# Sche_Main.net
KiCad netlist of a schematic drawn in Altium Designer
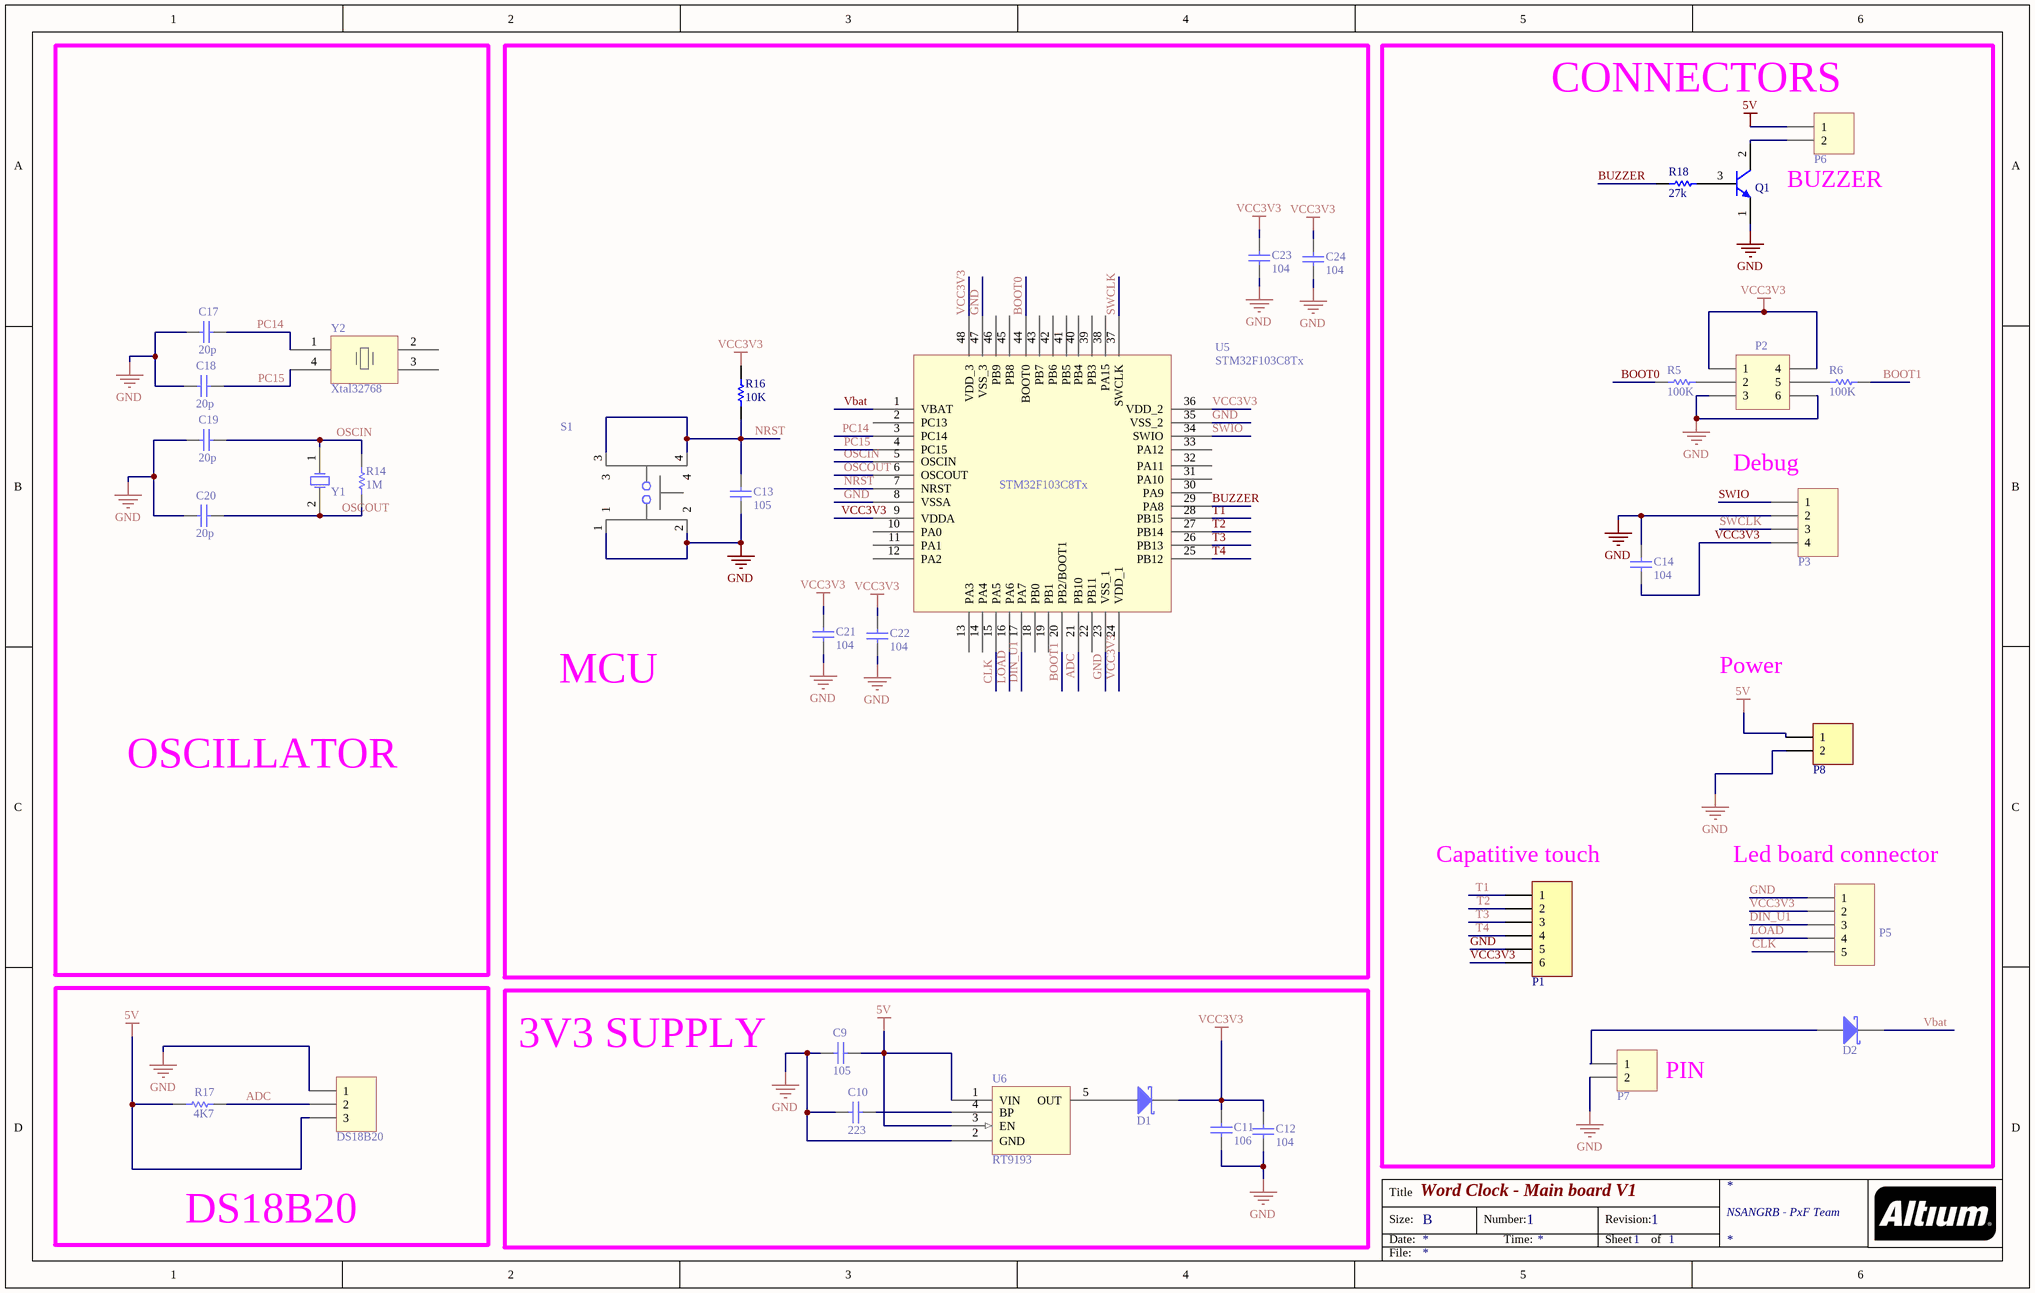
[diagram p0: Sche_Main.SchDoc]

(export (version "E")
  (design (tool "Eeschema 10.0.6"))
  (components
    (comp (ref "C9")
      (value "105")
      (footprint "CAP-SM-0805")
      (description "Capacitor")
      (fields (field (name "Comment") "Cap Non-Pol SMD"))
      (libsource (lib "PIF_Library") (part "Cap Non-Pol SMD"))
    )
    (comp (ref "C10")
      (value "223")
      (footprint "CAP-SM-0805")
      (description "Capacitor")
      (fields (field (name "Comment") "Cap Non-Pol SMD"))
      (libsource (lib "PIF_Library") (part "Cap Non-Pol SMD"))
    )
    (comp (ref "C11")
      (value "106")
      (footprint "CAP-SM-0805")
      (description "Capacitor")
      (fields (field (name "Comment") "Cap Non-Pol SMD"))
      (libsource (lib "PIF_Library") (part "Cap Non-Pol SMD"))
    )
    (comp (ref "C12")
      (value "104")
      (footprint "CAP-SM-0805")
      (description "Capacitor")
      (fields (field (name "Comment") "Cap Non-Pol SMD"))
      (libsource (lib "PIF_Library") (part "Cap Non-Pol SMD"))
    )
    (comp (ref "C13")
      (value "105")
      (footprint "CAP-SM-0805")
      (description "Capacitor")
      (fields (field (name "Comment") "Cap Non-Pol SMD"))
      (libsource (lib "PIF_Library") (part "Cap Non-Pol SMD"))
    )
    (comp (ref "C14")
      (value "104")
      (footprint "CAP-SM-0805")
      (description "Capacitor")
      (fields (field (name "Comment") "Cap Non-Pol SMD"))
      (libsource (lib "PIF_Library") (part "Cap Non-Pol SMD"))
    )
    (comp (ref "C17")
      (value "20p")
      (footprint "CAP-SM-0805")
      (description "Capacitor")
      (fields (field (name "Comment") "Cap Non-Pol SMD"))
      (libsource (lib "PIF_Library") (part "Cap Non-Pol SMD"))
    )
    (comp (ref "C18")
      (value "20p")
      (footprint "CAP-SM-0805")
      (description "Capacitor")
      (fields (field (name "Comment") "Cap Non-Pol SMD"))
      (libsource (lib "PIF_Library") (part "Cap Non-Pol SMD"))
    )
    (comp (ref "C19")
      (value "20p")
      (footprint "CAP-SM-0805")
      (description "Capacitor")
      (fields (field (name "Comment") "Cap Non-Pol SMD"))
      (libsource (lib "PIF_Library") (part "Cap Non-Pol SMD"))
    )
    (comp (ref "C20")
      (value "20p")
      (footprint "CAP-SM-0805")
      (description "Capacitor")
      (fields (field (name "Comment") "Cap Non-Pol SMD"))
      (libsource (lib "PIF_Library") (part "Cap Non-Pol SMD"))
    )
    (comp (ref "C21")
      (value "104")
      (footprint "CAP-SM-0805")
      (description "Capacitor")
      (fields (field (name "Comment") "Cap Non-Pol SMD"))
      (libsource (lib "PIF_Library") (part "Cap Non-Pol SMD"))
    )
    (comp (ref "C22")
      (value "104")
      (footprint "CAP-SM-0805")
      (description "Capacitor")
      (fields (field (name "Comment") "Cap Non-Pol SMD"))
      (libsource (lib "PIF_Library") (part "Cap Non-Pol SMD"))
    )
    (comp (ref "C23")
      (value "104")
      (footprint "CAP-SM-0805")
      (description "Capacitor")
      (fields (field (name "Comment") "Cap Non-Pol SMD"))
      (libsource (lib "PIF_Library") (part "Cap Non-Pol SMD"))
    )
    (comp (ref "C24")
      (value "104")
      (footprint "CAP-SM-0805")
      (description "Capacitor")
      (fields (field (name "Comment") "Cap Non-Pol SMD"))
      (libsource (lib "PIF_Library") (part "Cap Non-Pol SMD"))
    )
    (comp (ref "D1")
      (value "D Schottky")
      (footprint "SS34")
      (description "Schottky Diode")
      (fields (field (name "PUBLISHER") "Altium Limited"))
      (libsource (lib "PIF_Library") (part "D Schottky"))
    )
    (comp (ref "D2")
      (value "D Schottky")
      (footprint "SS34")
      (description "Schottky Diode")
      (fields (field (name "PUBLISHER") "Altium Limited"))
      (libsource (lib "PIF_Library") (part "D Schottky"))
    )
    (comp (ref "DS18B20")
      (value "Header 3")
      (footprint "QTO-92")
      (description "Header, 3-Pin")
      (fields (field (name "PUBLISHER") "Altium Limited"))
      (libsource (lib "PIF_Library") (part "Header 3"))
    )
    (comp (ref "P1")
      (value "Header 6")
      (footprint "JP6")
      (description "Header, 6-Pin")
      (fields (field (name "PUBLISHER") "Altium Limited"))
      (libsource (lib "PIF_Library") (part "Header 6"))
    )
    (comp (ref "P2")
      (value "Header 3X2")
      (footprint "JP3x2")
      (description "Header, 3-Pin, Dual row")
      (fields (field (name "PUBLISHER") "Altium Limited"))
      (libsource (lib "PIF_Library") (part "Header 3X2"))
    )
    (comp (ref "P3")
      (value "Header 4")
      (footprint "JP4")
      (description "Header, 4-Pin")
      (fields (field (name "PUBLISHER") "Altium Limited"))
      (libsource (lib "PIF_Library") (part "Header 4"))
    )
    (comp (ref "P5")
      (value "Header 5")
      (footprint "JP5")
      (description "Header, 5-Pin")
      (fields (field (name "PUBLISHER") "Altium Limited"))
      (libsource (lib "PIF_Library") (part "Header 5"))
    )
    (comp (ref "P6")
      (value "Domino 2")
      (footprint "JP2")
      (description "Domino, 2-Pin")
      (fields (field (name "PUBLISHER") "Altium Limited"))
      (libsource (lib "PIF_Library") (part "Domino 2"))
    )
    (comp (ref "P7")
      (value "Header 2")
      (footprint "JP2")
      (description "Header, 2-Pin")
      (fields (field (name "PUBLISHER") "Altium Limited"))
      (libsource (lib "PIF_Library") (part "Header 2"))
    )
    (comp (ref "P8")
      (value "Header 2")
      (footprint "JP2")
      (description "Header, 2-Pin")
      (fields (field (name "PUBLISHER") "Altium Limited"))
      (libsource (lib "PIF_Library") (part "Header 2"))
    )
    (comp (ref "Q1")
      (value "C1815")
      (footprint "SOT23B")
      (description "NPN Bipolar Transistor")
      (libsource (lib "PIF_Library") (part "C1815"))
    )
    (comp (ref "R5")
      (value "100K")
      (footprint "RES-SM-0805")
      (description "Resistor")
      (fields (field (name "Comment") "RESISTOR SMD"))
      (libsource (lib "PIF_Library") (part "RESISTOR SMD"))
    )
    (comp (ref "R6")
      (value "100K")
      (footprint "RES-SM-0805")
      (description "Resistor")
      (fields (field (name "Comment") "RESISTOR SMD"))
      (libsource (lib "PIF_Library") (part "RESISTOR SMD"))
    )
    (comp (ref "R14")
      (value "1M")
      (footprint "RES-SM-0805")
      (description "Resistor")
      (fields (field (name "Comment") "RESISTOR SMD"))
      (libsource (lib "PIF_Library") (part "RESISTOR SMD"))
    )
    (comp (ref "R16")
      (value "10K")
      (footprint "RES-SM-0805")
      (description "Resistor")
      (fields (field (name "Comment") "RESISTOR SMD"))
      (libsource (lib "PIF_Library") (part "RESISTOR SMD"))
    )
    (comp (ref "R17")
      (value "4K7")
      (footprint "RES-SM-0805")
      (description "Resistor")
      (fields (field (name "Comment") "RESISTOR SMD"))
      (libsource (lib "PIF_Library") (part "RESISTOR SMD"))
    )
    (comp (ref "R18")
      (value "27k")
      (footprint "RES-SM-0805")
      (description "Resistor")
      (fields (field (name "Comment") "RESISTOR SMD"))
      (libsource (lib "PIF_Library") (part "RESISTOR SMD"))
    )
    (comp (ref "S1")
      (value "TL3342F160QG")
      (footprint "SW_TL3342F160QG")
      (description "TL3342 Series SPST 1.6 N Round Button Gull Wing Surface Mount Tactile Switch")
      (fields (field (name "MF") "E-Switch"))
      (libsource (lib "TL3342F160QG") (part "TL3342F160QG"))
    )
    (comp (ref "U5")
      (value "STM32F103C8Tx")
      (footprint "TSQFP50P900X900X160-48N")
      (description "MCU 32-bit STM32F ARM Cortex M3 RISC 64KB Flash 2.5V/3.3V 48-Pin LQFP Tray")
      (fields
        (field (name "MANUFACTURER") "STMicroelectronics")
        (field (name "MANUFACTURER PART NUMBER") "STM32F103C8T6")
      )
      (libsource (lib "WC_Lib") (part "STM32F103C8Tx"))
    )
    (comp (ref "U6")
      (value "RT9193")
      (footprint "SOT95P279X129-5N")
      (description "RICHTEK         RT9193-15GB            IC, LDO, FIXED, 1.5V, 0.3A, SOT-23-5")
      (fields (field (name "MANUFACTURER") "Richtek") (field (name "MANUFACTURER PART NUMBER") "RT9193-15GB"))
      (libsource (lib "WC_Lib") (part "RT9193"))
    )
    (comp (ref "Y1")
      (value "XTAL")
      (footprint "XT2")
      (description "Crystal Oscillator")
      (fields (field (name "PUBLISHER") "Altium Limited"))
      (libsource (lib "PIF_Library") (part "XTAL"))
    )
    (comp (ref "Y2")
      (value "Xtal32768")
      (footprint "XTAL_ABS25-32.768KHZ-6-1-T")
      (libsource (lib "WC_Lib") (part "Xtal32768"))
    )
  )
  (nets
    (net (code "1") (name "/ADC") (class "Default")
      (node (ref "DS18B20") (pin "2") (pinfunction "2_2") (pintype "passive"))
      (node (ref "R17") (pin "2") (pinfunction "2_2") (pintype "passive"))
      (node (ref "U5") (pin "21") (pinfunction "PB10_21") (pintype "passive"))
    )
    (net (code "2") (name "/BOOT0") (class "Default")
      (node (ref "R5") (pin "1") (pinfunction "1_1") (pintype "passive"))
      (node (ref "U5") (pin "44") (pinfunction "BOOT0_44") (pintype "passive"))
    )
    (net (code "3") (name "/BOOT1") (class "Default")
      (node (ref "R6") (pin "2") (pinfunction "2_2") (pintype "passive"))
      (node (ref "U5") (pin "20") (pinfunction "PB2/BOOT1_20") (pintype "passive"))
    )
    (net (code "4") (name "/BUZZER") (class "Default")
      (node (ref "R18") (pin "1") (pinfunction "1_1") (pintype "passive"))
      (node (ref "U5") (pin "29") (pinfunction "PA8_29") (pintype "passive"))
    )
    (net (code "5") (name "/CLK") (class "Default")
      (node (ref "P5") (pin "5") (pinfunction "5_5") (pintype "passive"))
      (node (ref "U5") (pin "15") (pinfunction "PA5_15") (pintype "passive"))
    )
    (net (code "6") (name "/DIN_U1") (class "Default")
      (node (ref "P5") (pin "3") (pinfunction "3_3") (pintype "passive"))
      (node (ref "U5") (pin "17") (pinfunction "PA7_17") (pintype "passive"))
    )
    (net (code "7") (name "/LOAD") (class "Default")
      (node (ref "P5") (pin "4") (pinfunction "4_4") (pintype "passive"))
      (node (ref "U5") (pin "16") (pinfunction "PA6_16") (pintype "passive"))
    )
    (net (code "8") (name "/NRST") (class "Default")
      (node (ref "C13") (pin "2") (pinfunction "2_2") (pintype "passive"))
      (node (ref "R16") (pin "1") (pinfunction "1_1") (pintype "passive"))
      (node (ref "S1") (pin "3") (pinfunction "3_3") (pintype "passive"))
      (node (ref "S1") (pin "4") (pinfunction "4_4") (pintype "passive"))
      (node (ref "U5") (pin "7") (pinfunction "NRST_7") (pintype "passive"))
    )
    (net (code "9") (name "/OSCIN") (class "Default")
      (node (ref "C19") (pin "2") (pinfunction "2_2") (pintype "passive"))
      (node (ref "R14") (pin "2") (pinfunction "2_2") (pintype "passive"))
      (node (ref "U5") (pin "5") (pinfunction "OSCIN_5") (pintype "passive"))
      (node (ref "Y1") (pin "1") (pinfunction "OSC1_1") (pintype "passive"))
    )
    (net (code "10") (name "/OSCOUT") (class "Default")
      (node (ref "C20") (pin "2") (pinfunction "2_2") (pintype "passive"))
      (node (ref "R14") (pin "1") (pinfunction "1_1") (pintype "passive"))
      (node (ref "U5") (pin "6") (pinfunction "OSCOUT_6") (pintype "passive"))
      (node (ref "Y1") (pin "2") (pinfunction "OSC2_2") (pintype "passive"))
    )
    (net (code "11") (name "/PC14") (class "Default")
      (node (ref "C17") (pin "2") (pinfunction "2_2") (pintype "passive"))
      (node (ref "U5") (pin "3") (pinfunction "PC14_3") (pintype "passive"))
      (node (ref "Y2") (pin "1") (pinfunction "1_1") (pintype "passive"))
    )
    (net (code "12") (name "/PC15") (class "Default")
      (node (ref "C18") (pin "2") (pinfunction "2_2") (pintype "passive"))
      (node (ref "U5") (pin "4") (pinfunction "PC15_4") (pintype "passive"))
      (node (ref "Y2") (pin "4") (pinfunction "4_4") (pintype "passive"))
    )
    (net (code "13") (name "/SWCLK") (class "Default")
      (node (ref "P3") (pin "3") (pinfunction "3_3") (pintype "passive"))
      (node (ref "U5") (pin "37") (pinfunction "SWCLK_37") (pintype "passive"))
    )
    (net (code "14") (name "/SWIO") (class "Default")
      (node (ref "P3") (pin "1") (pinfunction "1_1") (pintype "passive"))
      (node (ref "U5") (pin "34") (pinfunction "SWIO_34") (pintype "passive"))
    )
    (net (code "15") (name "/T1") (class "Default")
      (node (ref "P1") (pin "1") (pinfunction "1_1") (pintype "passive"))
      (node (ref "U5") (pin "28") (pinfunction "PB15_28") (pintype "passive"))
    )
    (net (code "16") (name "/T2") (class "Default")
      (node (ref "P1") (pin "2") (pinfunction "2_2") (pintype "passive"))
      (node (ref "U5") (pin "27") (pinfunction "PB14_27") (pintype "passive"))
    )
    (net (code "17") (name "/T3") (class "Default")
      (node (ref "P1") (pin "3") (pinfunction "3_3") (pintype "passive"))
      (node (ref "U5") (pin "26") (pinfunction "PB13_26") (pintype "passive"))
    )
    (net (code "18") (name "/T4") (class "Default")
      (node (ref "P1") (pin "4") (pinfunction "4_4") (pintype "passive"))
      (node (ref "U5") (pin "25") (pinfunction "PB12_25") (pintype "passive"))
    )
    (net (code "19") (name "/Vbat") (class "Default")
      (node (ref "D2") (pin "2") (pinfunction "K_2") (pintype "passive"))
      (node (ref "U5") (pin "1") (pinfunction "VBAT_1") (pintype "passive"))
    )
    (net (code "20") (name "5V") (class "Default")
      (node (ref "C9") (pin "2") (pinfunction "2_2") (pintype "passive"))
      (node (ref "DS18B20") (pin "3") (pinfunction "3_3") (pintype "passive"))
      (node (ref "P6") (pin "1") (pinfunction "1_1") (pintype "passive"))
      (node (ref "P8") (pin "1") (pinfunction "1_1") (pintype "passive"))
      (node (ref "R17") (pin "1") (pinfunction "1_1") (pintype "passive"))
      (node (ref "U6") (pin "1") (pinfunction "VIN_1") (pintype "power_in"))
      (node (ref "U6") (pin "3") (pinfunction "EN_3") (pintype "input"))
    )
    (net (code "21") (name "GND") (class "Default")
      (node (ref "C10") (pin "1") (pinfunction "1_1") (pintype "passive"))
      (node (ref "C11") (pin "1") (pinfunction "1_1") (pintype "passive"))
      (node (ref "C12") (pin "1") (pinfunction "1_1") (pintype "passive"))
      (node (ref "C13") (pin "1") (pinfunction "1_1") (pintype "passive"))
      (node (ref "C14") (pin "2") (pinfunction "2_2") (pintype "passive"))
      (node (ref "C17") (pin "1") (pinfunction "1_1") (pintype "passive"))
      (node (ref "C18") (pin "1") (pinfunction "1_1") (pintype "passive"))
      (node (ref "C19") (pin "1") (pinfunction "1_1") (pintype "passive"))
      (node (ref "C20") (pin "1") (pinfunction "1_1") (pintype "passive"))
      (node (ref "C21") (pin "1") (pinfunction "1_1") (pintype "passive"))
      (node (ref "C22") (pin "1") (pinfunction "1_1") (pintype "passive"))
      (node (ref "C23") (pin "1") (pinfunction "1_1") (pintype "passive"))
      (node (ref "C24") (pin "1") (pinfunction "1_1") (pintype "passive"))
      (node (ref "C9") (pin "1") (pinfunction "1_1") (pintype "passive"))
      (node (ref "DS18B20") (pin "1") (pinfunction "1_1") (pintype "passive"))
      (node (ref "P1") (pin "5") (pinfunction "5_5") (pintype "passive"))
      (node (ref "P2") (pin "3") (pinfunction "3_3") (pintype "passive"))
      (node (ref "P2") (pin "6") (pinfunction "6_6") (pintype "passive"))
      (node (ref "P3") (pin "2") (pinfunction "2_2") (pintype "passive"))
      (node (ref "P5") (pin "1") (pinfunction "1_1") (pintype "passive"))
      (node (ref "P7") (pin "2") (pinfunction "2_2") (pintype "passive"))
      (node (ref "P8") (pin "2") (pinfunction "2_2") (pintype "passive"))
      (node (ref "Q1") (pin "1") (pinfunction "E_1") (pintype "passive"))
      (node (ref "S1") (pin "1") (pinfunction "1_1") (pintype "passive"))
      (node (ref "S1") (pin "2") (pinfunction "2_2") (pintype "passive"))
      (node (ref "U5") (pin "23") (pinfunction "VSS_1_23") (pintype "passive"))
      (node (ref "U5") (pin "35") (pinfunction "VSS_2_35") (pintype "passive"))
      (node (ref "U5") (pin "47") (pinfunction "VSS_3_47") (pintype "passive"))
      (node (ref "U5") (pin "8") (pinfunction "VSSA_8") (pintype "passive"))
      (node (ref "U6") (pin "2") (pinfunction "GND_2") (pintype "power_in"))
    )
    (net (code "22") (name "Net-(D1-A)") (class "Default")
      (node (ref "D1") (pin "1") (pinfunction "A_1") (pintype "passive"))
      (node (ref "U6") (pin "5") (pinfunction "OUT_5") (pintype "passive"))
    )
    (net (code "23") (name "Net-(D2-A)") (class "Default")
      (node (ref "D2") (pin "1") (pinfunction "A_1") (pintype "passive"))
      (node (ref "P7") (pin "1") (pinfunction "1_1") (pintype "passive"))
    )
    (net (code "24") (name "Net-(P2-Pad2)") (class "Default")
      (node (ref "P2") (pin "2") (pinfunction "2_2") (pintype "passive"))
      (node (ref "R5") (pin "2") (pinfunction "2_2") (pintype "passive"))
    )
    (net (code "25") (name "Net-(P2-Pad5)") (class "Default")
      (node (ref "P2") (pin "5") (pinfunction "5_5") (pintype "passive"))
      (node (ref "R6") (pin "1") (pinfunction "1_1") (pintype "passive"))
    )
    (net (code "26") (name "Net-(Q1-B)") (class "Default")
      (node (ref "Q1") (pin "3") (pinfunction "B_3") (pintype "passive"))
      (node (ref "R18") (pin "2") (pinfunction "2_2") (pintype "passive"))
    )
    (net (code "27") (name "Net-(Q1-C)") (class "Default")
      (node (ref "P6") (pin "2") (pinfunction "2_2") (pintype "passive"))
      (node (ref "Q1") (pin "2") (pinfunction "C_2") (pintype "passive"))
    )
    (net (code "28") (name "Net-(U6-BP)") (class "Default")
      (node (ref "C10") (pin "2") (pinfunction "2_2") (pintype "passive"))
      (node (ref "U6") (pin "4") (pinfunction "BP_4") (pintype "passive"))
    )
    (net (code "29") (name "VCC3V3") (class "Default")
      (node (ref "C11") (pin "2") (pinfunction "2_2") (pintype "passive"))
      (node (ref "C12") (pin "2") (pinfunction "2_2") (pintype "passive"))
      (node (ref "C14") (pin "1") (pinfunction "1_1") (pintype "passive"))
      (node (ref "C21") (pin "2") (pinfunction "2_2") (pintype "passive"))
      (node (ref "C22") (pin "2") (pinfunction "2_2") (pintype "passive"))
      (node (ref "C23") (pin "2") (pinfunction "2_2") (pintype "passive"))
      (node (ref "C24") (pin "2") (pinfunction "2_2") (pintype "passive"))
      (node (ref "D1") (pin "2") (pinfunction "K_2") (pintype "passive"))
      (node (ref "P1") (pin "6") (pinfunction "6_6") (pintype "passive"))
      (node (ref "P2") (pin "1") (pinfunction "1_1") (pintype "passive"))
      (node (ref "P2") (pin "4") (pinfunction "4_4") (pintype "passive"))
      (node (ref "P3") (pin "4") (pinfunction "4_4") (pintype "passive"))
      (node (ref "P5") (pin "2") (pinfunction "2_2") (pintype "passive"))
      (node (ref "R16") (pin "2") (pinfunction "2_2") (pintype "passive"))
      (node (ref "U5") (pin "24") (pinfunction "VDD_1_24") (pintype "passive"))
      (node (ref "U5") (pin "36") (pinfunction "VDD_2_36") (pintype "passive"))
      (node (ref "U5") (pin "48") (pinfunction "VDD_3_48") (pintype "passive"))
      (node (ref "U5") (pin "9") (pinfunction "VDDA_9") (pintype "passive"))
    )
    (net (code "30") (name "unconnected-(U5-PA0-Pad10)") (class "Default")
      (node (ref "U5") (pin "10") (pinfunction "PA0_10") (pintype "passive"))
    )
    (net (code "31") (name "unconnected-(U5-PA1-Pad11)") (class "Default")
      (node (ref "U5") (pin "11") (pinfunction "PA1_11") (pintype "passive"))
    )
    (net (code "32") (name "unconnected-(U5-PA2-Pad12)") (class "Default")
      (node (ref "U5") (pin "12") (pinfunction "PA2_12") (pintype "passive"))
    )
    (net (code "33") (name "unconnected-(U5-PA3-Pad13)") (class "Default")
      (node (ref "U5") (pin "13") (pinfunction "PA3_13") (pintype "passive"))
    )
    (net (code "34") (name "unconnected-(U5-PA4-Pad14)") (class "Default")
      (node (ref "U5") (pin "14") (pinfunction "PA4_14") (pintype "passive"))
    )
    (net (code "35") (name "unconnected-(U5-PA9-Pad30)") (class "Default")
      (node (ref "U5") (pin "30") (pinfunction "PA9_30") (pintype "passive"))
    )
    (net (code "36") (name "unconnected-(U5-PA10-Pad31)") (class "Default")
      (node (ref "U5") (pin "31") (pinfunction "PA10_31") (pintype "passive"))
    )
    (net (code "37") (name "unconnected-(U5-PA11-Pad32)") (class "Default")
      (node (ref "U5") (pin "32") (pinfunction "PA11_32") (pintype "passive"))
    )
    (net (code "38") (name "unconnected-(U5-PA12-Pad33)") (class "Default")
      (node (ref "U5") (pin "33") (pinfunction "PA12_33") (pintype "passive"))
    )
    (net (code "39") (name "unconnected-(U5-PA15-Pad38)") (class "Default")
      (node (ref "U5") (pin "38") (pinfunction "PA15_38") (pintype "passive"))
    )
    (net (code "40") (name "unconnected-(U5-PB0-Pad18)") (class "Default")
      (node (ref "U5") (pin "18") (pinfunction "PB0_18") (pintype "passive"))
    )
    (net (code "41") (name "unconnected-(U5-PB1-Pad19)") (class "Default")
      (node (ref "U5") (pin "19") (pinfunction "PB1_19") (pintype "passive"))
    )
    (net (code "42") (name "unconnected-(U5-PB3-Pad39)") (class "Default")
      (node (ref "U5") (pin "39") (pinfunction "PB3_39") (pintype "passive"))
    )
    (net (code "43") (name "unconnected-(U5-PB4-Pad40)") (class "Default")
      (node (ref "U5") (pin "40") (pinfunction "PB4_40") (pintype "passive"))
    )
    (net (code "44") (name "unconnected-(U5-PB5-Pad41)") (class "Default")
      (node (ref "U5") (pin "41") (pinfunction "PB5_41") (pintype "passive"))
    )
    (net (code "45") (name "unconnected-(U5-PB6-Pad42)") (class "Default")
      (node (ref "U5") (pin "42") (pinfunction "PB6_42") (pintype "passive"))
    )
    (net (code "46") (name "unconnected-(U5-PB7-Pad43)") (class "Default")
      (node (ref "U5") (pin "43") (pinfunction "PB7_43") (pintype "passive"))
    )
    (net (code "47") (name "unconnected-(U5-PB8-Pad45)") (class "Default")
      (node (ref "U5") (pin "45") (pinfunction "PB8_45") (pintype "passive"))
    )
    (net (code "48") (name "unconnected-(U5-PB9-Pad46)") (class "Default")
      (node (ref "U5") (pin "46") (pinfunction "PB9_46") (pintype "passive"))
    )
    (net (code "49") (name "unconnected-(U5-PB11-Pad22)") (class "Default")
      (node (ref "U5") (pin "22") (pinfunction "PB11_22") (pintype "passive"))
    )
    (net (code "50") (name "unconnected-(U5-PC13-Pad2)") (class "Default")
      (node (ref "U5") (pin "2") (pinfunction "PC13_2") (pintype "passive"))
    )
    (net (code "51") (name "unconnected-(Y2-Pad2)") (class "Default")
      (node (ref "Y2") (pin "2") (pinfunction "2_2") (pintype "passive"))
    )
    (net (code "52") (name "unconnected-(Y2-Pad3)") (class "Default")
      (node (ref "Y2") (pin "3") (pinfunction "3_3") (pintype "passive"))
    )
  )
)
